# 200429_eAR_ECU_MPS20_PX_Sensor_PTH_R00.net
KiCad netlist of a schematic drawn in EAGLE
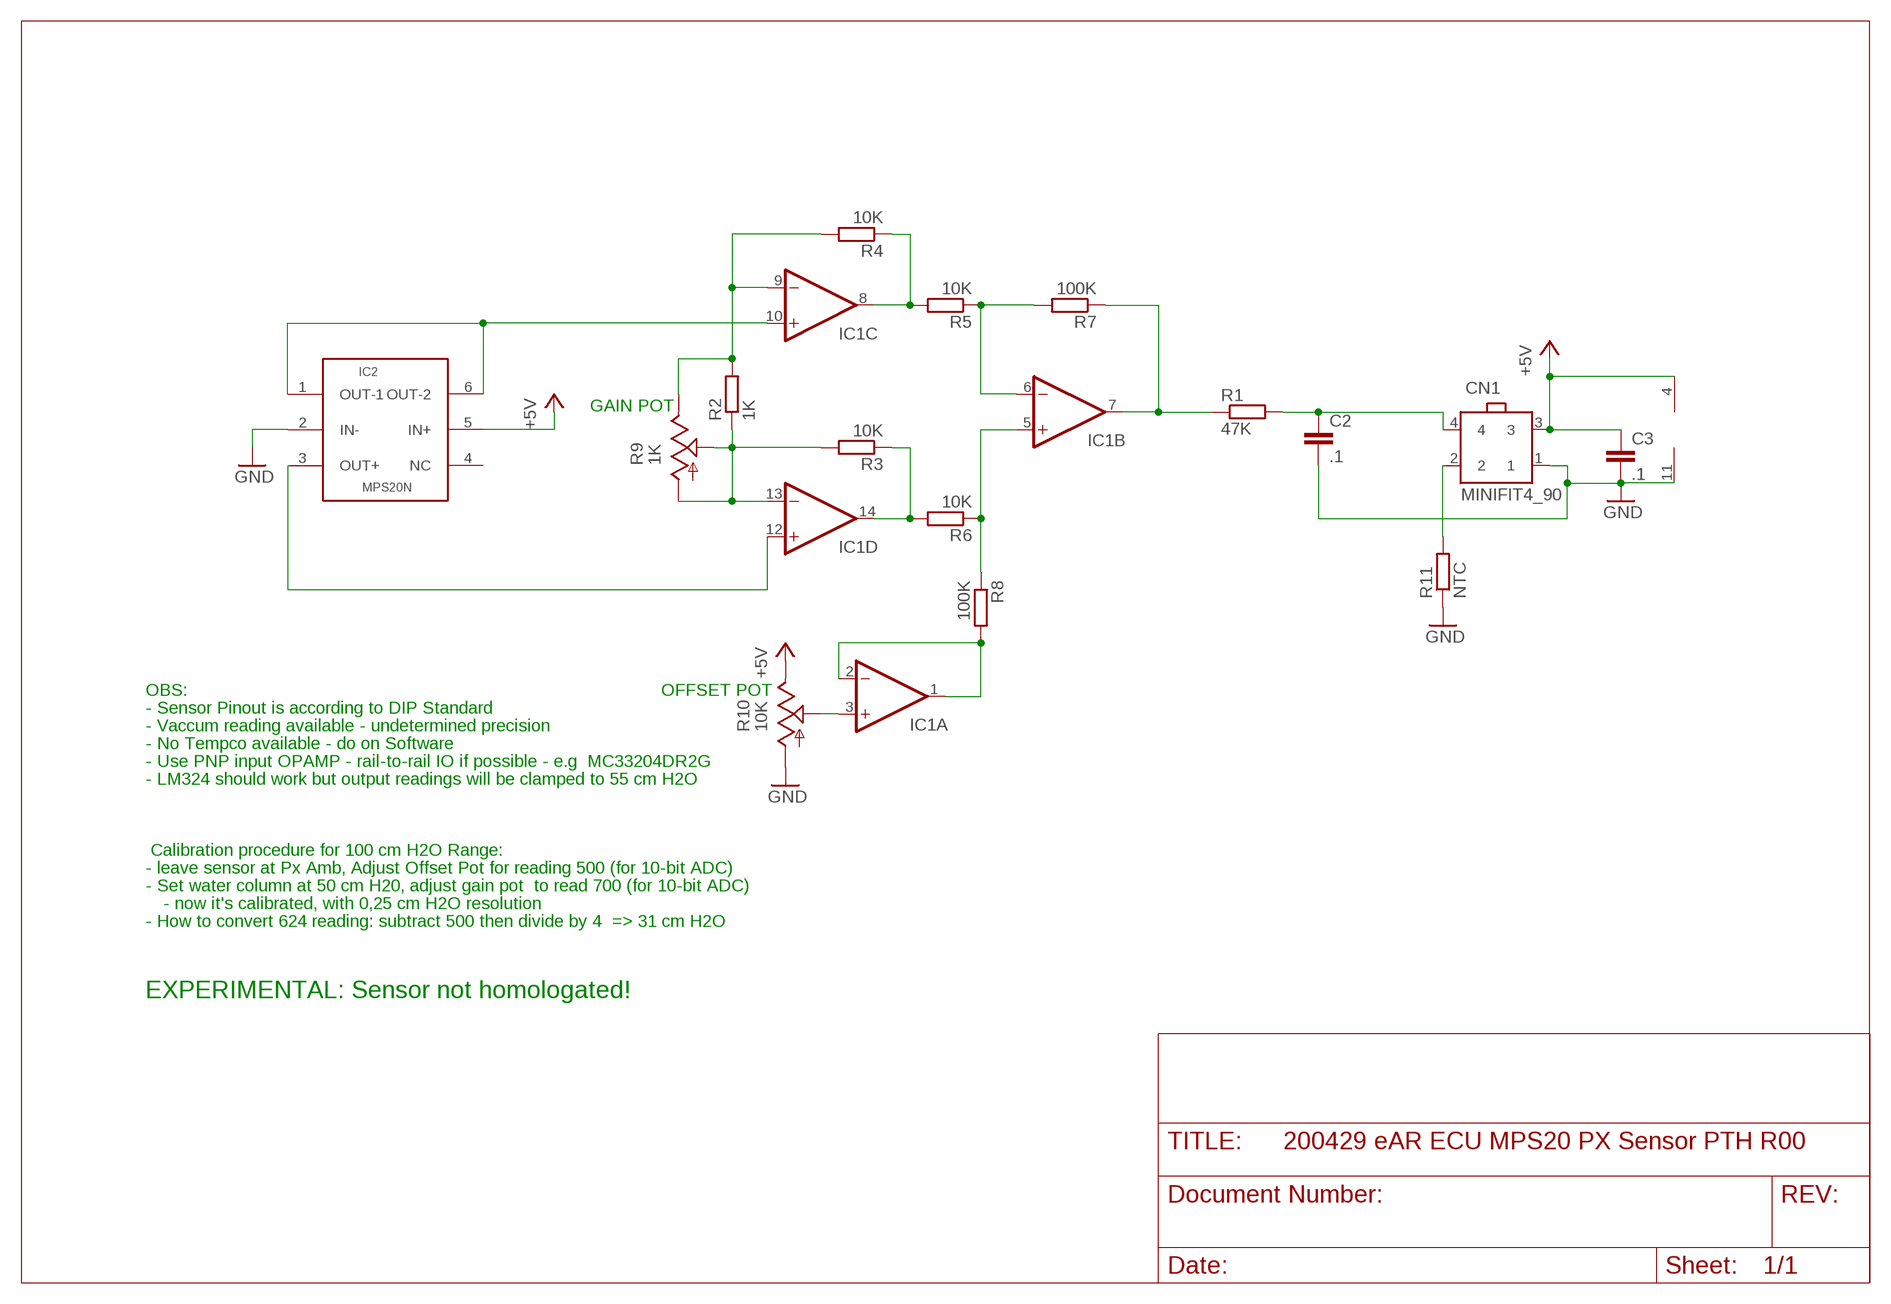
[diagram p0: schematic, sheet 1]

(export (version "E")
  (design (tool "Eeschema 10.0.6"))
  (components
    (comp (ref "C2")
      (value ".1")
      (footprint "eagle-import:C050-025X075")
      (libsource (lib "eagle-import") (part "C-EU050-025X075"))
    )
    (comp (ref "C3")
      (value ".1")
      (footprint "eagle-import:C050-025X075")
      (libsource (lib "eagle-import") (part "C-EU050-025X075"))
    )
    (comp (ref "CN1")
      (value "MINIFIT4_90")
      (footprint "eagle-import:MINIFIT4_90")
      (libsource (lib "eagle-import") (part "MINIFIT4_90"))
    )
    (comp (ref "IC1")
      (value "LM324N")
      (footprint "eagle-import:DIL14")
      (libsource (lib "eagle-import") (part "LM324N"))
    )
    (comp (ref "IC2")
      (value "MPS20N")
      (footprint "eagle-import:DIL6-WIDE")
      (libsource (lib "eagle-import") (part "MPS20N"))
    )
    (comp (ref "R1")
      (value "47K")
      (footprint "eagle-import:0207_10")
      (libsource (lib "eagle-import") (part "R-EU_0207/10"))
    )
    (comp (ref "R2")
      (value "1K")
      (footprint "eagle-import:0207_10")
      (libsource (lib "eagle-import") (part "R-EU_0207/10"))
    )
    (comp (ref "R3")
      (value "10K")
      (footprint "eagle-import:0207_10")
      (libsource (lib "eagle-import") (part "R-EU_0207/10"))
    )
    (comp (ref "R4")
      (value "10K")
      (footprint "eagle-import:0207_10")
      (libsource (lib "eagle-import") (part "R-EU_0207/10"))
    )
    (comp (ref "R5")
      (value "10K")
      (footprint "eagle-import:0207_10")
      (libsource (lib "eagle-import") (part "R-EU_0207/10"))
    )
    (comp (ref "R6")
      (value "10K")
      (footprint "eagle-import:0207_10")
      (libsource (lib "eagle-import") (part "R-EU_0207/10"))
    )
    (comp (ref "R7")
      (value "100K")
      (footprint "eagle-import:0207_10")
      (libsource (lib "eagle-import") (part "R-EU_0207/10"))
    )
    (comp (ref "R8")
      (value "100K")
      (footprint "eagle-import:0207_10")
      (libsource (lib "eagle-import") (part "R-EU_0207/10"))
    )
    (comp (ref "R9")
      (value "1K")
      (footprint "eagle-import:B64Y")
      (libsource (lib "eagle-import") (part "TRIM_US-B64Y"))
    )
    (comp (ref "R10")
      (value "10K")
      (footprint "eagle-import:B64Y")
      (libsource (lib "eagle-import") (part "TRIM_US-B64Y"))
    )
    (comp (ref "R11")
      (value "NTC")
      (footprint "eagle-import:R0805W")
      (libsource (lib "eagle-import") (part "R-EU_R0805W"))
    )
  )
  (nets
    (net (code "1") (name "+5V") (class "Default")
      (node (ref "C3") (pin "1") (pinfunction "1_1") (pintype "passive"))
      (node (ref "CN1") (pin "3") (pinfunction "3_3") (pintype "bidirectional"))
      (node (ref "IC1") (pin "4") (pinfunction "V+_4") (pintype "power_in"))
      (node (ref "IC2") (pin "5") (pinfunction "IN+_5") (pintype "bidirectional"))
      (node (ref "R10") (pin "E") (pinfunction "E_E") (pintype "passive"))
    )
    (net (code "2") (name "GND") (class "Default")
      (node (ref "C2") (pin "2") (pinfunction "2_2") (pintype "passive"))
      (node (ref "C3") (pin "2") (pinfunction "2_2") (pintype "passive"))
      (node (ref "CN1") (pin "1") (pinfunction "1_1") (pintype "bidirectional"))
      (node (ref "IC1") (pin "11") (pinfunction "V-_11") (pintype "power_in"))
      (node (ref "IC2") (pin "2") (pinfunction "IN-_2") (pintype "bidirectional"))
      (node (ref "R10") (pin "A") (pinfunction "A_A") (pintype "passive"))
      (node (ref "R11") (pin "1") (pinfunction "1_1") (pintype "passive"))
    )
    (net (code "3") (name "Net-(C2-Pad1)") (class "Default")
      (node (ref "C2") (pin "1") (pinfunction "1_1") (pintype "passive"))
      (node (ref "CN1") (pin "4") (pinfunction "4_4") (pintype "bidirectional"))
      (node (ref "R1") (pin "2") (pinfunction "2_2") (pintype "passive"))
    )
    (net (code "4") (name "Net-(CN1-Pad2)") (class "Default")
      (node (ref "CN1") (pin "2") (pinfunction "2_2") (pintype "bidirectional"))
      (node (ref "R11") (pin "2") (pinfunction "2_2") (pintype "passive"))
    )
    (net (code "5") (name "Net-(IC1A-+IN)") (class "Default")
      (node (ref "IC1") (pin "3") (pinfunction "+IN_3") (pintype "input"))
      (node (ref "R10") (pin "S") (pinfunction "S_S") (pintype "passive"))
    )
    (net (code "6") (name "Net-(IC1A--IN)") (class "Default")
      (node (ref "IC1") (pin "1") (pinfunction "OUT_1") (pintype "output"))
      (node (ref "IC1") (pin "2") (pinfunction "-IN_2") (pintype "input"))
      (node (ref "R8") (pin "2") (pinfunction "2_2") (pintype "passive"))
    )
    (net (code "7") (name "Net-(IC1B-+IN)") (class "Default")
      (node (ref "IC1") (pin "5") (pinfunction "+IN_5") (pintype "input"))
      (node (ref "R6") (pin "1") (pinfunction "1_1") (pintype "passive"))
      (node (ref "R8") (pin "1") (pinfunction "1_1") (pintype "passive"))
    )
    (net (code "8") (name "Net-(IC1B--IN)") (class "Default")
      (node (ref "IC1") (pin "6") (pinfunction "-IN_6") (pintype "input"))
      (node (ref "R5") (pin "1") (pinfunction "1_1") (pintype "passive"))
      (node (ref "R7") (pin "2") (pinfunction "2_2") (pintype "passive"))
    )
    (net (code "9") (name "Net-(IC1B-OUT)") (class "Default")
      (node (ref "IC1") (pin "7") (pinfunction "OUT_7") (pintype "output"))
      (node (ref "R1") (pin "1") (pinfunction "1_1") (pintype "passive"))
      (node (ref "R7") (pin "1") (pinfunction "1_1") (pintype "passive"))
    )
    (net (code "10") (name "Net-(IC1C-+IN)") (class "Default")
      (node (ref "IC1") (pin "10") (pinfunction "+IN_10") (pintype "input"))
      (node (ref "IC2") (pin "1") (pinfunction "OUT-1_1") (pintype "bidirectional"))
      (node (ref "IC2") (pin "6") (pinfunction "OUT-2_6") (pintype "bidirectional"))
    )
    (net (code "11") (name "Net-(IC1C--IN)") (class "Default")
      (node (ref "IC1") (pin "9") (pinfunction "-IN_9") (pintype "input"))
      (node (ref "R2") (pin "2") (pinfunction "2_2") (pintype "passive"))
      (node (ref "R4") (pin "2") (pinfunction "2_2") (pintype "passive"))
      (node (ref "R9") (pin "E") (pinfunction "E_E") (pintype "passive"))
    )
    (net (code "12") (name "Net-(IC1C-OUT)") (class "Default")
      (node (ref "IC1") (pin "8") (pinfunction "OUT_8") (pintype "output"))
      (node (ref "R4") (pin "1") (pinfunction "1_1") (pintype "passive"))
      (node (ref "R5") (pin "2") (pinfunction "2_2") (pintype "passive"))
    )
    (net (code "13") (name "Net-(IC1D-+IN)") (class "Default")
      (node (ref "IC1") (pin "12") (pinfunction "+IN_12") (pintype "input"))
      (node (ref "IC2") (pin "3") (pinfunction "OUT+_3") (pintype "bidirectional"))
    )
    (net (code "14") (name "Net-(IC1D--IN)") (class "Default")
      (node (ref "IC1") (pin "13") (pinfunction "-IN_13") (pintype "input"))
      (node (ref "R2") (pin "1") (pinfunction "1_1") (pintype "passive"))
      (node (ref "R3") (pin "2") (pinfunction "2_2") (pintype "passive"))
      (node (ref "R9") (pin "A") (pinfunction "A_A") (pintype "passive"))
      (node (ref "R9") (pin "S") (pinfunction "S_S") (pintype "passive"))
    )
    (net (code "15") (name "Net-(IC1D-OUT)") (class "Default")
      (node (ref "IC1") (pin "14") (pinfunction "OUT_14") (pintype "output"))
      (node (ref "R3") (pin "1") (pinfunction "1_1") (pintype "passive"))
      (node (ref "R6") (pin "2") (pinfunction "2_2") (pintype "passive"))
    )
    (net (code "16") (name "unconnected-(IC2-NC-Pad4)") (class "Default")
      (node (ref "IC2") (pin "4") (pinfunction "NC_4") (pintype "bidirectional"))
    )
  )
)
